# ps.net
KiCad netlist of a schematic drawn in EAGLE
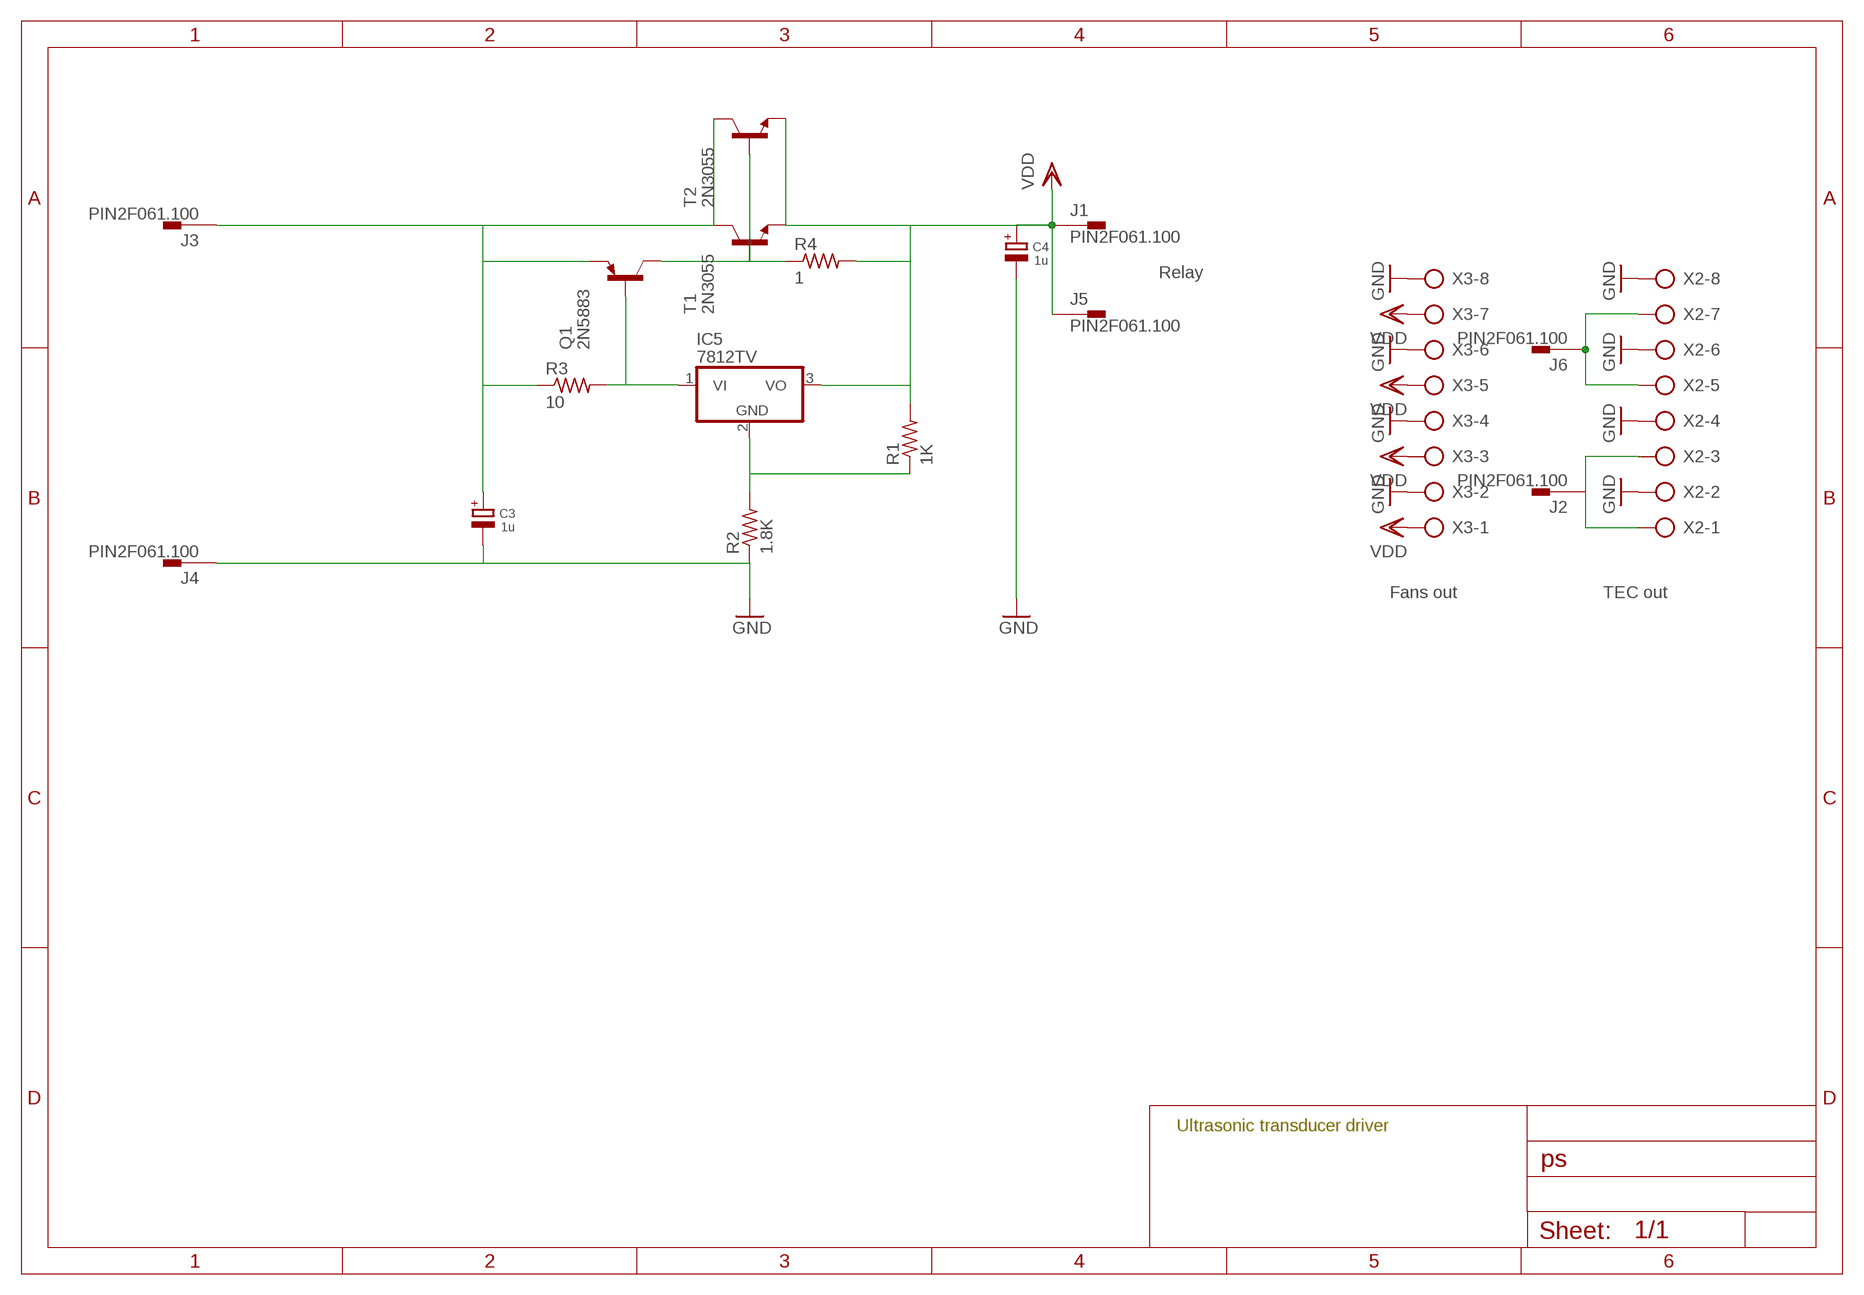
[diagram p0: schematic, sheet 1]

(export (version "E")
  (design (tool "Eeschema 10.0.6"))
  (components
    (comp (ref "C3")
      (value "1u")
      (footprint "eagle-import:EB20D")
      (libsource (lib "eagle-import") (part "CPOL-EUE10-20"))
    )
    (comp (ref "C4")
      (value "1u")
      (footprint "eagle-import:EB20D")
      (libsource (lib "eagle-import") (part "CPOL-EUE10-20"))
    )
    (comp (ref "IC5")
      (value "7812TV")
      (footprint "eagle-import:TO220V")
      (libsource (lib "eagle-import") (part "78TV12"))
    )
    (comp (ref "J1")
      (value "PIN2F061.100")
      (footprint "eagle-import:F061.100")
      (libsource (lib "eagle-import") (part "PIN2F061.100"))
    )
    (comp (ref "J2")
      (value "PIN2F061.100")
      (footprint "eagle-import:F061.100")
      (libsource (lib "eagle-import") (part "PIN2F061.100"))
    )
    (comp (ref "J3")
      (value "PIN2F061.100")
      (footprint "eagle-import:F061.100")
      (libsource (lib "eagle-import") (part "PIN2F061.100"))
    )
    (comp (ref "J4")
      (value "PIN2F061.100")
      (footprint "eagle-import:F061.100")
      (libsource (lib "eagle-import") (part "PIN2F061.100"))
    )
    (comp (ref "J5")
      (value "PIN2F061.100")
      (footprint "eagle-import:F061.100")
      (libsource (lib "eagle-import") (part "PIN2F061.100"))
    )
    (comp (ref "J6")
      (value "PIN2F061.100")
      (footprint "eagle-import:F061.100")
      (libsource (lib "eagle-import") (part "PIN2F061.100"))
    )
    (comp (ref "Q1")
      (value "2N5883")
      (footprint "eagle-import:TO3")
      (libsource (lib "eagle-import") (part "2N4905"))
    )
    (comp (ref "R1")
      (value "1K")
      (footprint "eagle-import:0207_15")
      (libsource (lib "eagle-import") (part "R-US_0207/15"))
    )
    (comp (ref "R2")
      (value "1.8K")
      (footprint "eagle-import:0207_15")
      (libsource (lib "eagle-import") (part "R-US_0207/15"))
    )
    (comp (ref "R3")
      (value "10")
      (footprint "eagle-import:0207_15")
      (libsource (lib "eagle-import") (part "R-US_0207/15"))
    )
    (comp (ref "R4")
      (value "1")
      (footprint "eagle-import:0922_22")
      (libsource (lib "eagle-import") (part "R-US_0922/22"))
    )
    (comp (ref "T1")
      (value "2N3055")
      (footprint "eagle-import:TO3")
      (libsource (lib "eagle-import") (part "2N3055"))
    )
    (comp (ref "T2")
      (value "2N3055")
      (footprint "eagle-import:TO3")
      (libsource (lib "eagle-import") (part "2N3055"))
    )
    (comp (ref "X2")
      (value "AK300/8")
      (footprint "eagle-import:AK300_8")
      (libsource (lib "eagle-import") (part "AK300/8"))
    )
    (comp (ref "X3")
      (value "AK300/8")
      (footprint "eagle-import:AK300_8")
      (libsource (lib "eagle-import") (part "AK300/8"))
    )
  )
  (nets
    (net (code "1") (name "GND") (class "Default")
      (node (ref "C3") (pin "-") (pinfunction "-_-") (pintype "passive"))
      (node (ref "C4") (pin "-") (pinfunction "-_-") (pintype "passive"))
      (node (ref "J4") (pin "A1") (pinfunction "1_A1") (pintype "passive"))
      (node (ref "J4") (pin "A2") (pinfunction "1_A2") (pintype "passive"))
      (node (ref "R2") (pin "1") (pinfunction "1_1") (pintype "passive"))
      (node (ref "X2") (pin "2") (pinfunction "KL_2") (pintype "passive"))
      (node (ref "X2") (pin "4") (pinfunction "KL_4") (pintype "passive"))
      (node (ref "X2") (pin "6") (pinfunction "KL_6") (pintype "passive"))
      (node (ref "X2") (pin "8") (pinfunction "KL_8") (pintype "passive"))
      (node (ref "X3") (pin "2") (pinfunction "KL_2") (pintype "passive"))
      (node (ref "X3") (pin "4") (pinfunction "KL_4") (pintype "passive"))
      (node (ref "X3") (pin "6") (pinfunction "KL_6") (pintype "passive"))
      (node (ref "X3") (pin "8") (pinfunction "KL_8") (pintype "passive"))
    )
    (net (code "2") (name "Net-(C3-Pad+)") (class "Default")
      (node (ref "C3") (pin "+") (pinfunction "+_+") (pintype "passive"))
      (node (ref "J3") (pin "A1") (pinfunction "1_A1") (pintype "passive"))
      (node (ref "J3") (pin "A2") (pinfunction "1_A2") (pintype "passive"))
      (node (ref "Q1") (pin "E") (pinfunction "E_E") (pintype "passive"))
      (node (ref "R3") (pin "1") (pinfunction "1_1") (pintype "passive"))
      (node (ref "T1") (pin "C") (pinfunction "C_C") (pintype "passive"))
      (node (ref "T1") (pin "C/") (pinfunction "C_C/") (pintype "passive"))
      (node (ref "T2") (pin "C") (pinfunction "C_C") (pintype "passive"))
      (node (ref "T2") (pin "C/") (pinfunction "C_C/") (pintype "passive"))
    )
    (net (code "3") (name "Net-(IC5-GND)") (class "Default")
      (node (ref "IC5") (pin "2") (pinfunction "GND_2") (pintype "passive"))
      (node (ref "R1") (pin "1") (pinfunction "1_1") (pintype "passive"))
      (node (ref "R2") (pin "2") (pinfunction "2_2") (pintype "passive"))
    )
    (net (code "4") (name "Net-(IC5-VI)") (class "Default")
      (node (ref "IC5") (pin "1") (pinfunction "VI_1") (pintype "input"))
      (node (ref "Q1") (pin "B") (pinfunction "B_B") (pintype "passive"))
      (node (ref "R3") (pin "2") (pinfunction "2_2") (pintype "passive"))
    )
    (net (code "5") (name "Net-(Q1-C-PadC{slash})") (class "Default")
      (node (ref "Q1") (pin "C") (pinfunction "C_C") (pintype "passive"))
      (node (ref "Q1") (pin "C/") (pinfunction "C_C/") (pintype "passive"))
      (node (ref "R4") (pin "1") (pinfunction "1_1") (pintype "passive"))
      (node (ref "T1") (pin "B") (pinfunction "B_B") (pintype "passive"))
      (node (ref "T2") (pin "B") (pinfunction "B_B") (pintype "passive"))
    )
    (net (code "6") (name "Net-(X2A-KL)") (class "Default")
      (node (ref "J2") (pin "A1") (pinfunction "1_A1") (pintype "passive"))
      (node (ref "J2") (pin "A2") (pinfunction "1_A2") (pintype "passive"))
      (node (ref "X2") (pin "1") (pinfunction "KL_1") (pintype "passive"))
      (node (ref "X2") (pin "3") (pinfunction "KL_3") (pintype "passive"))
    )
    (net (code "7") (name "Net-(X2E-KL)") (class "Default")
      (node (ref "J6") (pin "A1") (pinfunction "1_A1") (pintype "passive"))
      (node (ref "J6") (pin "A2") (pinfunction "1_A2") (pintype "passive"))
      (node (ref "X2") (pin "5") (pinfunction "KL_5") (pintype "passive"))
      (node (ref "X2") (pin "7") (pinfunction "KL_7") (pintype "passive"))
    )
    (net (code "8") (name "VDD") (class "Default")
      (node (ref "C4") (pin "+") (pinfunction "+_+") (pintype "passive"))
      (node (ref "IC5") (pin "3") (pinfunction "VO_3") (pintype "passive"))
      (node (ref "J1") (pin "A1") (pinfunction "1_A1") (pintype "passive"))
      (node (ref "J1") (pin "A2") (pinfunction "1_A2") (pintype "passive"))
      (node (ref "J5") (pin "A1") (pinfunction "1_A1") (pintype "passive"))
      (node (ref "J5") (pin "A2") (pinfunction "1_A2") (pintype "passive"))
      (node (ref "R1") (pin "2") (pinfunction "2_2") (pintype "passive"))
      (node (ref "R4") (pin "2") (pinfunction "2_2") (pintype "passive"))
      (node (ref "T1") (pin "E") (pinfunction "E_E") (pintype "passive"))
      (node (ref "T2") (pin "E") (pinfunction "E_E") (pintype "passive"))
      (node (ref "X3") (pin "1") (pinfunction "KL_1") (pintype "passive"))
      (node (ref "X3") (pin "3") (pinfunction "KL_3") (pintype "passive"))
      (node (ref "X3") (pin "5") (pinfunction "KL_5") (pintype "passive"))
      (node (ref "X3") (pin "7") (pinfunction "KL_7") (pintype "passive"))
    )
  )
)
